# Power.net
KiCad netlist of a schematic drawn in Altium Designer
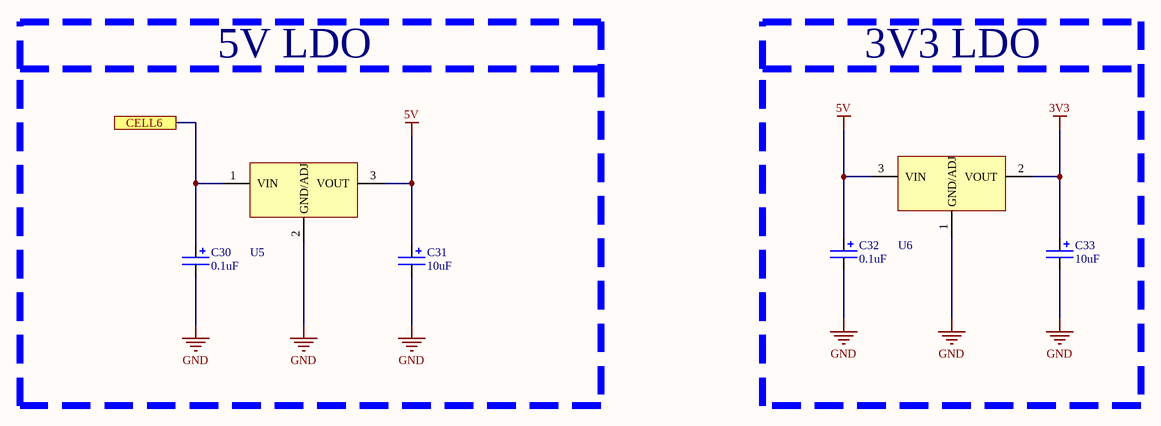
[diagram p0: Power.SchDoc]

(export (version "E")
  (design (tool "Eeschema 10.0.6"))
  (components
    (comp (ref "C30")
      (value "0.1uF")
      (footprint "CAP 0603")
      (description "Multilayer Ceramic Capacitor")
      (fields (field (name "Comment") "CAP 0603"))
      (libsource (lib "Kaptanyums Lib") (part "CAP 0603"))
    )
    (comp (ref "C31")
      (value "10uF")
      (footprint "CAP 0603")
      (description "Multilayer Ceramic Capacitor")
      (fields (field (name "Comment") "CAP 0603"))
      (libsource (lib "Kaptanyums Lib") (part "CAP 0603"))
    )
    (comp (ref "C32")
      (value "0.1uF")
      (footprint "CAP 0603")
      (description "Multilayer Ceramic Capacitor")
      (fields (field (name "Comment") "CAP 0603"))
      (libsource (lib "Kaptanyums Lib") (part "CAP 0603"))
    )
    (comp (ref "C33")
      (value "10uF")
      (footprint "CAP 0603")
      (description "Multilayer Ceramic Capacitor")
      (fields (field (name "Comment") "CAP 0603"))
      (libsource (lib "Kaptanyums Lib") (part "CAP 0603"))
    )
    (comp (ref "U5")
      (value "LM7805MPX")
      (footprint "SOT223-3")
      (description "Regulator Linear")
      (libsource (lib "Kaptanyums Lib") (part "LM7805MPX"))
    )
    (comp (ref "U6")
      (value "LD1117AS33")
      (footprint "SOT223-3")
      (description "Regulator Linear")
      (libsource (lib "Kaptanyums Lib") (part "LD1117AS33"))
    )
  )
  (nets
    (net (code "1") (name "/CELL6") (class "Default")
      (node (ref "C30") (pin "1") (pinfunction "1_1") (pintype "passive"))
      (node (ref "U5") (pin "1") (pinfunction "VIN_1") (pintype "passive"))
    )
    (net (code "2") (name "3V3") (class "Default")
      (node (ref "C33") (pin "1") (pinfunction "1_1") (pintype "passive"))
      (node (ref "U6") (pin "2") (pinfunction "VOUT_2") (pintype "passive"))
    )
    (net (code "3") (name "5V") (class "Default")
      (node (ref "C31") (pin "1") (pinfunction "1_1") (pintype "passive"))
      (node (ref "C32") (pin "1") (pinfunction "1_1") (pintype "passive"))
      (node (ref "U5") (pin "3") (pinfunction "VOUT_3") (pintype "passive"))
      (node (ref "U6") (pin "3") (pinfunction "VIN_3") (pintype "passive"))
    )
    (net (code "4") (name "GND") (class "Default")
      (node (ref "C30") (pin "2") (pinfunction "2_2") (pintype "passive"))
      (node (ref "C31") (pin "2") (pinfunction "2_2") (pintype "passive"))
      (node (ref "C32") (pin "2") (pinfunction "2_2") (pintype "passive"))
      (node (ref "C33") (pin "2") (pinfunction "2_2") (pintype "passive"))
      (node (ref "U5") (pin "2") (pinfunction "GND/ADJ_2") (pintype "passive"))
      (node (ref "U6") (pin "1") (pinfunction "GND/ADJ_1") (pintype "passive"))
    )
  )
)
